# buck.net
KiCad netlist of a schematic drawn in Altium Designer
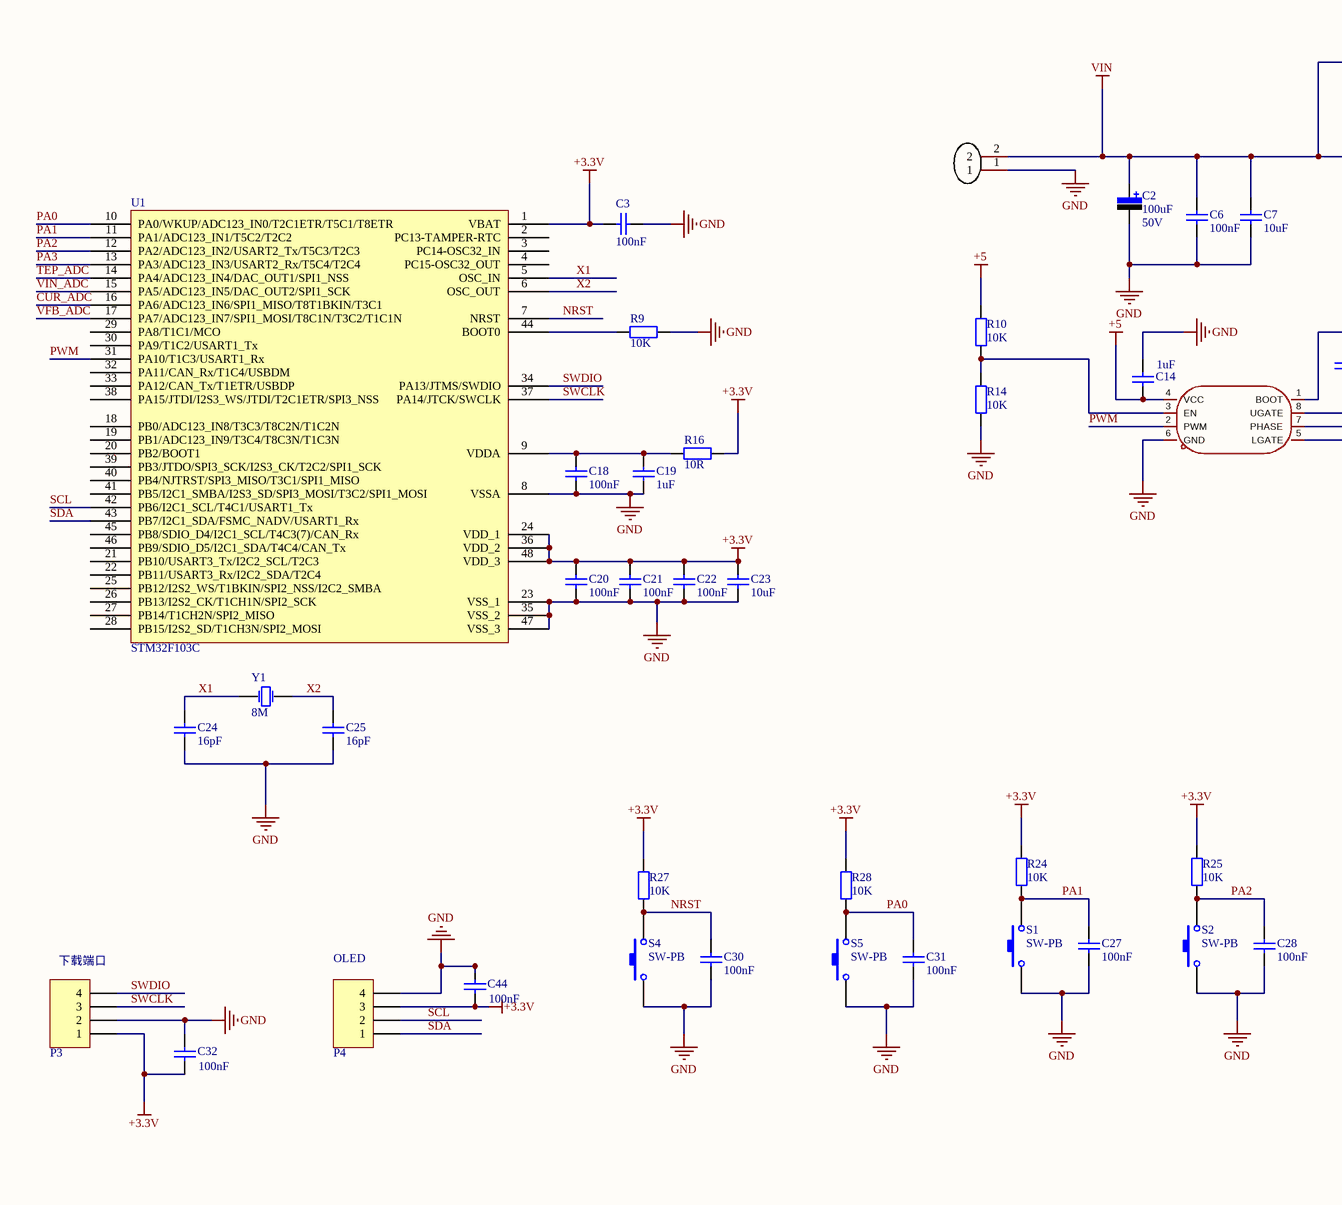
[diagram p0: buck.SchDoc, left]
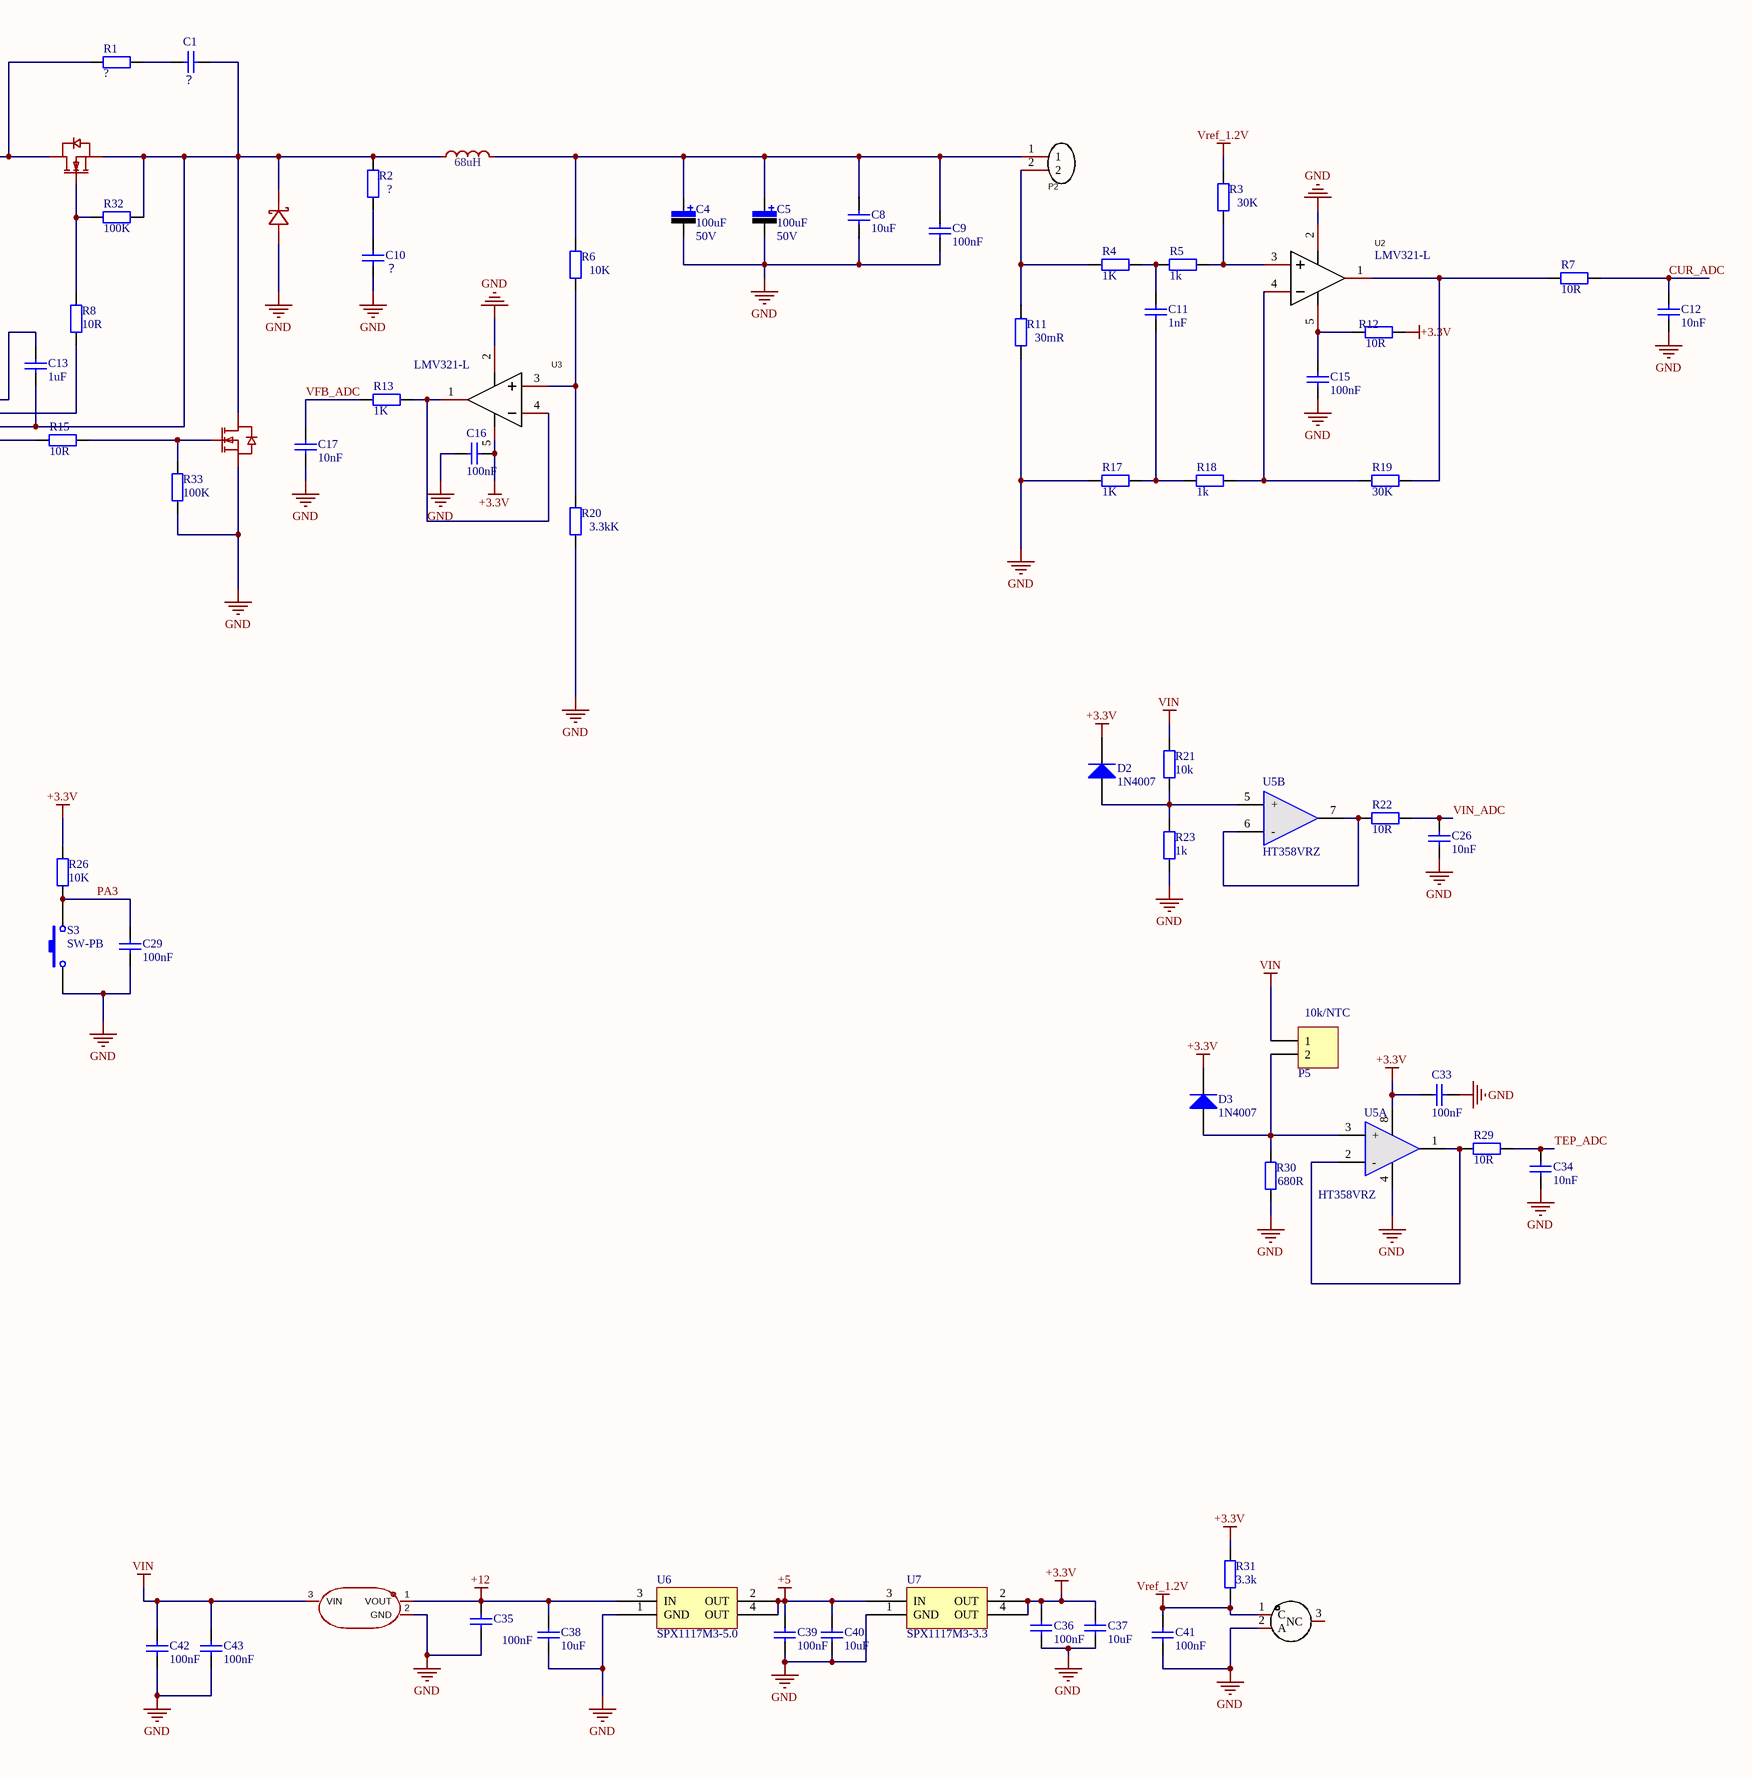
[diagram p1: buck.SchDoc, right]

(export (version "E")
  (design (tool "Eeschema 10.0.6"))
  (components
    (comp (ref "C1")
      (value "？")
      (footprint "C-RAD-0603")
      (description "无极性电容")
      (fields (field (name "PUBLISHER") "Altium Limited"))
      (libsource (lib "fszhang") (part "Cap"))
    )
    (comp (ref "C2")
      (value "100uF")
      (footprint "CAP-TH_BD6.0-P2.50-D0.5-FD")
      (description "极性电解电容")
      (fields
        (field (name "VOL") "50V")
        (field (name "Comment") "Cap Pol")
        (field (name "PUBLISHER") "Altium Limited")
      )
      (libsource (lib "fszhang") (part "Cap Pol"))
    )
    (comp (ref "C3")
      (value "100nF")
      (footprint "C-RAD-0603")
      (description "无极性电容")
      (fields (field (name "PUBLISHER") "Altium Limited"))
      (libsource (lib "fszhang") (part "Cap"))
    )
    (comp (ref "C4")
      (value "100uF")
      (footprint "CAP-TH_BD6.0-P2.50-D0.5-FD")
      (description "极性电解电容")
      (fields
        (field (name "VOL") "50V")
        (field (name "Comment") "Cap Pol")
        (field (name "PUBLISHER") "Altium Limited")
      )
      (libsource (lib "fszhang") (part "Cap Pol"))
    )
    (comp (ref "C5")
      (value "100uF")
      (footprint "CAP-TH_BD6.0-P2.50-D0.5-FD")
      (description "极性电解电容")
      (fields
        (field (name "VOL") "50V")
        (field (name "Comment") "Cap Pol")
        (field (name "PUBLISHER") "Altium Limited")
      )
      (libsource (lib "fszhang") (part "Cap Pol"))
    )
    (comp (ref "C6")
      (value "100nF")
      (footprint "C-RAD-0603")
      (description "无极性电容")
      (fields (field (name "PUBLISHER") "Altium Limited"))
      (libsource (lib "fszhang") (part "Cap"))
    )
    (comp (ref "C7")
      (value "10uF")
      (footprint "C-RAD-0603")
      (description "无极性电容")
      (fields (field (name "PUBLISHER") "Altium Limited"))
      (libsource (lib "fszhang") (part "Cap"))
    )
    (comp (ref "C8")
      (value "10uF")
      (footprint "C-RAD-0603")
      (description "无极性电容")
      (fields (field (name "PUBLISHER") "Altium Limited"))
      (libsource (lib "fszhang") (part "Cap"))
    )
    (comp (ref "C9")
      (value "100nF")
      (footprint "C-RAD-0603")
      (description "无极性电容")
      (fields (field (name "PUBLISHER") "Altium Limited"))
      (libsource (lib "fszhang") (part "Cap"))
    )
    (comp (ref "C10")
      (value "？")
      (footprint "C-RAD-0603")
      (description "无极性电容")
      (fields (field (name "PUBLISHER") "Altium Limited"))
      (libsource (lib "fszhang") (part "Cap"))
    )
    (comp (ref "C11")
      (value "1nF")
      (footprint "C-RAD-0603")
      (description "无极性电容")
      (fields (field (name "PUBLISHER") "Altium Limited"))
      (libsource (lib "fszhang") (part "Cap"))
    )
    (comp (ref "C12")
      (value "10nF")
      (footprint "C-RAD-0603")
      (description "无极性电容")
      (fields (field (name "PUBLISHER") "Altium Limited"))
      (libsource (lib "fszhang") (part "Cap"))
    )
    (comp (ref "C13")
      (value "1uF")
      (footprint "C-RAD-0603")
      (description "无极性电容")
      (fields (field (name "PUBLISHER") "Altium Limited"))
      (libsource (lib "fszhang") (part "Cap"))
    )
    (comp (ref "C14")
      (value "1uF")
      (footprint "C-RAD-0603")
      (description "无极性电容")
      (fields (field (name "PUBLISHER") "Altium Limited"))
      (libsource (lib "fszhang") (part "Cap"))
    )
    (comp (ref "C15")
      (value "100nF")
      (footprint "C-RAD-0603")
      (description "无极性电容")
      (fields (field (name "PUBLISHER") "Altium Limited"))
      (libsource (lib "fszhang") (part "Cap"))
    )
    (comp (ref "C16")
      (value "100nF")
      (footprint "C-RAD-0603")
      (description "无极性电容")
      (fields (field (name "PUBLISHER") "Altium Limited"))
      (libsource (lib "fszhang") (part "Cap"))
    )
    (comp (ref "C17")
      (value "10nF")
      (footprint "C-RAD-0603")
      (description "无极性电容")
      (fields (field (name "PUBLISHER") "Altium Limited"))
      (libsource (lib "fszhang") (part "Cap"))
    )
    (comp (ref "C18")
      (value "100nF")
      (footprint "C-RAD-0603")
      (description "无极性电容")
      (fields (field (name "PUBLISHER") "Altium Limited"))
      (libsource (lib "fszhang") (part "Cap"))
    )
    (comp (ref "C19")
      (value "1uF")
      (footprint "C-RAD-0603")
      (description "无极性电容")
      (fields (field (name "PUBLISHER") "Altium Limited"))
      (libsource (lib "fszhang") (part "Cap"))
    )
    (comp (ref "C20")
      (value "100nF")
      (footprint "C-RAD-0603")
      (description "无极性电容")
      (fields (field (name "PUBLISHER") "Altium Limited"))
      (libsource (lib "fszhang") (part "Cap"))
    )
    (comp (ref "C21")
      (value "100nF")
      (footprint "C-RAD-0603")
      (description "无极性电容")
      (fields (field (name "PUBLISHER") "Altium Limited"))
      (libsource (lib "fszhang") (part "Cap"))
    )
    (comp (ref "C22")
      (value "100nF")
      (footprint "C-RAD-0603")
      (description "无极性电容")
      (fields (field (name "PUBLISHER") "Altium Limited"))
      (libsource (lib "fszhang") (part "Cap"))
    )
    (comp (ref "C23")
      (value "10uF")
      (footprint "C-RAD-0603")
      (description "无极性电容")
      (fields (field (name "PUBLISHER") "Altium Limited"))
      (libsource (lib "fszhang") (part "Cap"))
    )
    (comp (ref "C24")
      (value "16pF")
      (footprint "C-RAD-0603")
      (description "无极性电容")
      (fields (field (name "PUBLISHER") "Altium Limited"))
      (libsource (lib "fszhang") (part "Cap"))
    )
    (comp (ref "C25")
      (value "16pF")
      (footprint "C-RAD-0603")
      (description "无极性电容")
      (fields (field (name "PUBLISHER") "Altium Limited"))
      (libsource (lib "fszhang") (part "Cap"))
    )
    (comp (ref "C26")
      (value "10nF")
      (footprint "C-RAD-0603")
      (description "无极性电容")
      (fields (field (name "PUBLISHER") "Altium Limited"))
      (libsource (lib "fszhang") (part "Cap"))
    )
    (comp (ref "C27")
      (value "100nF")
      (footprint "C-RAD-0603")
      (description "无极性电容")
      (fields (field (name "PUBLISHER") "Altium Limited"))
      (libsource (lib "fszhang") (part "Cap"))
    )
    (comp (ref "C28")
      (value "100nF")
      (footprint "C-RAD-0603")
      (description "无极性电容")
      (fields (field (name "PUBLISHER") "Altium Limited"))
      (libsource (lib "fszhang") (part "Cap"))
    )
    (comp (ref "C29")
      (value "100nF")
      (footprint "C-RAD-0603")
      (description "无极性电容")
      (fields (field (name "PUBLISHER") "Altium Limited"))
      (libsource (lib "fszhang") (part "Cap"))
    )
    (comp (ref "C30")
      (value "100nF")
      (footprint "C-RAD-0603")
      (description "无极性电容")
      (fields (field (name "PUBLISHER") "Altium Limited"))
      (libsource (lib "fszhang") (part "Cap"))
    )
    (comp (ref "C31")
      (value "100nF")
      (footprint "C-RAD-0603")
      (description "无极性电容")
      (fields (field (name "PUBLISHER") "Altium Limited"))
      (libsource (lib "fszhang") (part "Cap"))
    )
    (comp (ref "C32")
      (value "100nF")
      (footprint "C-RAD-0603")
      (description "无极性电容")
      (fields (field (name "PUBLISHER") "Altium Limited"))
      (libsource (lib "fszhang") (part "Cap"))
    )
    (comp (ref "C33")
      (value "100nF")
      (footprint "C-RAD-0603")
      (description "无极性电容")
      (fields (field (name "PUBLISHER") "Altium Limited"))
      (libsource (lib "fszhang") (part "Cap"))
    )
    (comp (ref "C34")
      (value "10nF")
      (footprint "C-RAD-0603")
      (description "无极性电容")
      (fields (field (name "PUBLISHER") "Altium Limited"))
      (libsource (lib "fszhang") (part "Cap"))
    )
    (comp (ref "C35")
      (value "100nF")
      (footprint "C-RAD-0603")
      (description "无极性电容")
      (fields (field (name "PUBLISHER") "Altium Limited"))
      (libsource (lib "fszhang") (part "Cap"))
    )
    (comp (ref "C36")
      (value "100nF")
      (footprint "C-RAD-0603")
      (description "无极性电容")
      (fields (field (name "PUBLISHER") "Altium Limited"))
      (libsource (lib "fszhang") (part "Cap"))
    )
    (comp (ref "C37")
      (value "10uF")
      (footprint "C-RAD-0603")
      (description "无极性电容")
      (fields (field (name "PUBLISHER") "Altium Limited"))
      (libsource (lib "fszhang") (part "Cap"))
    )
    (comp (ref "C38")
      (value "10uF")
      (footprint "C-RAD-0603")
      (description "无极性电容")
      (fields (field (name "PUBLISHER") "Altium Limited"))
      (libsource (lib "fszhang") (part "Cap"))
    )
    (comp (ref "C39")
      (value "100nF")
      (footprint "C-RAD-0603")
      (description "无极性电容")
      (fields (field (name "PUBLISHER") "Altium Limited"))
      (libsource (lib "fszhang") (part "Cap"))
    )
    (comp (ref "C40")
      (value "10uF")
      (footprint "C-RAD-0603")
      (description "无极性电容")
      (fields (field (name "PUBLISHER") "Altium Limited"))
      (libsource (lib "fszhang") (part "Cap"))
    )
    (comp (ref "C41")
      (value "100nF")
      (footprint "C-RAD-0603")
      (description "无极性电容")
      (fields (field (name "PUBLISHER") "Altium Limited"))
      (libsource (lib "fszhang") (part "Cap"))
    )
    (comp (ref "C42")
      (value "100nF")
      (footprint "C-RAD-0603")
      (description "无极性电容")
      (fields (field (name "PUBLISHER") "Altium Limited"))
      (libsource (lib "fszhang") (part "Cap"))
    )
    (comp (ref "C43")
      (value "100nF")
      (footprint "C-RAD-0603")
      (description "无极性电容")
      (fields (field (name "PUBLISHER") "Altium Limited"))
      (libsource (lib "fszhang") (part "Cap"))
    )
    (comp (ref "C44")
      (value "100nF")
      (footprint "C-RAD-0603")
      (description "无极性电容")
      (fields (field (name "PUBLISHER") "Altium Limited"))
      (libsource (lib "fszhang") (part "Cap"))
    )
    (comp (ref "D1")
      (value "ss54f_c18199179")
      (footprint "SMAF_L3.5-W2.6-LS4.7-RD-1")
      (description "二极管配置:独立式;正向压降(Vf):550mV@5.0A;直流反向耐压(Vr):40V;整流电流:5A;")
      (fields (field (name "MANUFACTURER") "R+O(宏嘉诚)") (field (name "MANUFACTURERPART") "SS54F"))
      (libsource (lib "fszhang") (part "SS54F"))
    )
    (comp (ref "D2")
      (value "Diode")
      (footprint "SMA_L4.3-W2.6-LS5.0-FD")
      (description "二极管")
      (fields (field (name "TYPE") "1N4007") (field (name "PUBLISHER") "Altium Limited"))
      (libsource (lib "fszhang") (part "Diode"))
    )
    (comp (ref "D3")
      (value "Diode")
      (footprint "SMA_L4.3-W2.6-LS5.0-FD")
      (description "二极管")
      (fields (field (name "TYPE") "1N4007") (field (name "PUBLISHER") "Altium Limited"))
      (libsource (lib "fszhang") (part "Diode"))
    )
    (comp (ref "L1")
      (value "68uH")
      (footprint "IND-SMD_L11.5-W10.1_XR1050-680M")
      (description "电感值:68uH;精度:±20%;额定电流:3A;饱和电流(Isat):3.8A;")
      (fields (field (name "MANUFACTURER") "XR(祥如)") (field (name "MANUFACTURERPART") "XR1050-680M"))
      (libsource (lib "fszhang") (part "xr1050-680m"))
    )
    (comp (ref "P1")
      (value "WJ500V-5.08-2P")
      (footprint "CONN-TH_2P-P5.00_WJ500V-5.08-2P")
      (description "接线端子")
      (fields (field (name "MANUFACTURER") "KANGNEX(康奈克斯电气)"))
      (libsource (lib "fszhang") (part "WJ500V-5.08-2P"))
    )
    (comp (ref "P2")
      (value "WJ500V-5.08-2P")
      (footprint "CONN-TH_2P-P5.00_WJ500V-5.08-2P")
      (description "接线端子")
      (fields (field (name "MANUFACTURER") "KANGNEX(康奈克斯电气)"))
      (libsource (lib "fszhang") (part "WJ500V-5.08-2P"))
    )
    (comp (ref "P3")
      (value "Header 4")
      (footprint "HDR4X1_A")
      (description "接插件")
      (fields (field (name "PUBLISHER") "Altium Limited"))
      (libsource (lib "fszhang") (part "Header 4"))
    )
    (comp (ref "P4")
      (value "Header 4")
      (footprint "HDR4X1_A")
      (description "接插件")
      (fields (field (name "PUBLISHER") "Altium Limited"))
      (libsource (lib "fszhang") (part "Header 4"))
    )
    (comp (ref "P5")
      (value "Header 2")
      (footprint "HDR2X1_A")
      (description "接插件")
      (fields (field (name "PUBLISHER") "Altium Limited"))
      (libsource (lib "fszhang") (part "Header 2"))
    )
    (comp (ref "Q1")
      (value "xr20n04")
      (footprint "TO-252-3L_L6.6-W6.1-P4.60-LS9.5-BR-CW")
      (description "数量:1个N沟道;漏源电压(Vdss):40V;连续漏极电流(Id):20A;导通电阻(RDS(on)):40mΩ@10V;耗散功率(Pd):4W;阈值电压(Vgs(th)):2.2V;")
      (fields (field (name "MANUFACTURER") "XNRUSEMI(新锐)") (field (name "MANUFACTURERPART") "XR20N04"))
      (libsource (lib "fszhang") (part "XR20N04"))
    )
    (comp (ref "Q2")
      (value "xr20n04")
      (footprint "TO-252-3L_L6.6-W6.1-P4.60-LS9.5-BR-CW")
      (description "数量:1个N沟道;漏源电压(Vdss):40V;连续漏极电流(Id):20A;导通电阻(RDS(on)):40mΩ@10V;耗散功率(Pd):4W;阈值电压(Vgs(th)):2.2V;")
      (fields (field (name "MANUFACTURER") "XNRUSEMI(新锐)") (field (name "MANUFACTURERPART") "XR20N04"))
      (libsource (lib "fszhang") (part "XR20N04"))
    )
    (comp (ref "R1")
      (value "?")
      (footprint "0603-1")
      (description "贴片电阻")
      (fields (field (name "PUBLISHER") "Altium Limited"))
      (libsource (lib "fszhang") (part "Res1"))
    )
    (comp (ref "R2")
      (value "?")
      (footprint "0603-1")
      (description "贴片电阻")
      (fields (field (name "PUBLISHER") "Altium Limited"))
      (libsource (lib "") (part "Res1_2"))
    )
    (comp (ref "R3")
      (value "30K")
      (footprint "0603-1")
      (description "贴片电阻")
      (fields (field (name "PUBLISHER") "Altium Limited"))
      (libsource (lib "") (part "Res1_2"))
    )
    (comp (ref "R4")
      (value "1K")
      (footprint "0603-1")
      (description "贴片电阻")
      (fields (field (name "PUBLISHER") "Altium Limited"))
      (libsource (lib "fszhang") (part "Res1"))
    )
    (comp (ref "R5")
      (value "1k")
      (footprint "0603-1")
      (description "贴片电阻")
      (fields (field (name "PUBLISHER") "Altium Limited"))
      (libsource (lib "fszhang") (part "Res1"))
    )
    (comp (ref "R6")
      (value "10K")
      (footprint "0603-1")
      (description "贴片电阻")
      (fields (field (name "PUBLISHER") "Altium Limited"))
      (libsource (lib "") (part "Res1_2"))
    )
    (comp (ref "R7")
      (value "10R")
      (footprint "0603-1")
      (description "贴片电阻")
      (fields (field (name "PUBLISHER") "Altium Limited"))
      (libsource (lib "") (part "Res1_2"))
    )
    (comp (ref "R8")
      (value "10R")
      (footprint "0603-1")
      (description "贴片电阻")
      (fields (field (name "PUBLISHER") "Altium Limited"))
      (libsource (lib "") (part "Res1_2"))
    )
    (comp (ref "R9")
      (value "10K")
      (footprint "0603-1")
      (description "贴片电阻")
      (fields (field (name "PUBLISHER") "Altium Limited"))
      (libsource (lib "") (part "Res1_1"))
    )
    (comp (ref "R10")
      (value "10K")
      (footprint "0603-1")
      (description "贴片电阻")
      (fields (field (name "PUBLISHER") "Altium Limited"))
      (libsource (lib "") (part "Res1_3"))
    )
    (comp (ref "R11")
      (value "30mR")
      (footprint "2512")
      (description "贴片电阻")
      (fields (field (name "PUBLISHER") "Altium Limited"))
      (libsource (lib "") (part "Res1_2"))
    )
    (comp (ref "R12")
      (value "10R")
      (footprint "0603-1")
      (description "贴片电阻")
      (fields (field (name "PUBLISHER") "Altium Limited"))
      (libsource (lib "fszhang") (part "Res1"))
    )
    (comp (ref "R13")
      (value "1K")
      (footprint "0603-1")
      (description "贴片电阻")
      (fields (field (name "PUBLISHER") "Altium Limited"))
      (libsource (lib "fszhang") (part "Res1"))
    )
    (comp (ref "R14")
      (value "10K")
      (footprint "0603-1")
      (description "贴片电阻")
      (fields (field (name "PUBLISHER") "Altium Limited"))
      (libsource (lib "") (part "Res1_3"))
    )
    (comp (ref "R15")
      (value "10R")
      (footprint "0603-1")
      (description "贴片电阻")
      (fields (field (name "PUBLISHER") "Altium Limited"))
      (libsource (lib "fszhang") (part "Res1"))
    )
    (comp (ref "R16")
      (value "10R")
      (footprint "0603-1")
      (description "贴片电阻")
      (fields (field (name "PUBLISHER") "Altium Limited"))
      (libsource (lib "") (part "Res1_1"))
    )
    (comp (ref "R17")
      (value "1K")
      (footprint "0603-1")
      (description "贴片电阻")
      (fields (field (name "PUBLISHER") "Altium Limited"))
      (libsource (lib "fszhang") (part "Res1"))
    )
    (comp (ref "R18")
      (value "1k")
      (footprint "0603-1")
      (description "贴片电阻")
      (fields (field (name "PUBLISHER") "Altium Limited"))
      (libsource (lib "fszhang") (part "Res1"))
    )
    (comp (ref "R19")
      (value "30K")
      (footprint "0603-1")
      (description "贴片电阻")
      (fields (field (name "PUBLISHER") "Altium Limited"))
      (libsource (lib "fszhang") (part "Res1"))
    )
    (comp (ref "R20")
      (value "3.3kK")
      (footprint "0603-1")
      (description "贴片电阻")
      (fields (field (name "PUBLISHER") "Altium Limited"))
      (libsource (lib "") (part "Res1_2"))
    )
    (comp (ref "R21")
      (value "10k")
      (footprint "0603-1")
      (description "贴片电阻")
      (fields (field (name "PUBLISHER") "Altium Limited"))
      (libsource (lib "") (part "Res1_3"))
    )
    (comp (ref "R22")
      (value "10R")
      (footprint "0603-1")
      (description "贴片电阻")
      (fields (field (name "PUBLISHER") "Altium Limited"))
      (libsource (lib "") (part "Res1_1"))
    )
    (comp (ref "R23")
      (value "1k")
      (footprint "0603-1")
      (description "贴片电阻")
      (fields (field (name "PUBLISHER") "Altium Limited"))
      (libsource (lib "") (part "Res1_3"))
    )
    (comp (ref "R24")
      (value "10K")
      (footprint "0603-1")
      (description "贴片电阻")
      (fields (field (name "PUBLISHER") "Altium Limited"))
      (libsource (lib "") (part "Res1_2"))
    )
    (comp (ref "R25")
      (value "10K")
      (footprint "0603-1")
      (description "贴片电阻")
      (fields (field (name "PUBLISHER") "Altium Limited"))
      (libsource (lib "") (part "Res1_2"))
    )
    (comp (ref "R26")
      (value "10K")
      (footprint "0603-1")
      (description "贴片电阻")
      (fields (field (name "PUBLISHER") "Altium Limited"))
      (libsource (lib "") (part "Res1_2"))
    )
    (comp (ref "R27")
      (value "10K")
      (footprint "0603-1")
      (description "贴片电阻")
      (fields (field (name "PUBLISHER") "Altium Limited"))
      (libsource (lib "") (part "Res1_2"))
    )
    (comp (ref "R28")
      (value "10K")
      (footprint "0603-1")
      (description "贴片电阻")
      (fields (field (name "PUBLISHER") "Altium Limited"))
      (libsource (lib "") (part "Res1_2"))
    )
    (comp (ref "R29")
      (value "10R")
      (footprint "0603-1")
      (description "贴片电阻")
      (fields (field (name "PUBLISHER") "Altium Limited"))
      (libsource (lib "") (part "Res1_1"))
    )
    (comp (ref "R30")
      (value "680R")
      (footprint "0603-1")
      (description "贴片电阻")
      (fields (field (name "PUBLISHER") "Altium Limited"))
      (libsource (lib "") (part "Res1_3"))
    )
    (comp (ref "R31")
      (value "3.3k")
      (footprint "0603-1")
      (description "贴片电阻")
      (fields (field (name "PUBLISHER") "Altium Limited"))
      (libsource (lib "") (part "Res1_1"))
    )
    (comp (ref "R32")
      (value "100K")
      (footprint "0603-1")
      (description "贴片电阻")
      (fields (field (name "PUBLISHER") "Altium Limited"))
      (libsource (lib "fszhang") (part "Res1"))
    )
    (comp (ref "R33")
      (value "100K")
      (footprint "0603-1")
      (description "贴片电阻")
      (fields (field (name "PUBLISHER") "Altium Limited"))
      (libsource (lib "") (part "Res1_3"))
    )
    (comp (ref "S1")
      (value "SW-PB")
      (footprint "SW_PB2_A1")
      (description "微动开关")
      (fields (field (name "PUBLISHER") "Altium Limited"))
      (libsource (lib "fszhang") (part "SW-PB"))
    )
    (comp (ref "S2")
      (value "SW-PB")
      (footprint "SW_PB2_A1")
      (description "微动开关")
      (fields (field (name "PUBLISHER") "Altium Limited"))
      (libsource (lib "fszhang") (part "SW-PB"))
    )
    (comp (ref "S3")
      (value "SW-PB")
      (footprint "SW_PB2_A1")
      (description "微动开关")
      (fields (field (name "PUBLISHER") "Altium Limited"))
      (libsource (lib "fszhang") (part "SW-PB"))
    )
    (comp (ref "S4")
      (value "SW-PB")
      (footprint "SW_PB2_A1")
      (description "微动开关")
      (fields (field (name "PUBLISHER") "Altium Limited"))
      (libsource (lib "fszhang") (part "SW-PB"))
    )
    (comp (ref "S5")
      (value "SW-PB")
      (footprint "SW_PB2_A1")
      (description "微动开关")
      (fields (field (name "PUBLISHER") "Altium Limited"))
      (libsource (lib "fszhang") (part "SW-PB"))
    )
    (comp (ref "U1")
      (value "STM32F103C")
      (footprint "LQFP-48_M")
      (description "STM32单片机48引脚")
      (libsource (lib "fszhang") (part "STM32F103C"))
    )
    (comp (ref "U2")
      (value "LMV321-L")
      (footprint "SOT-23-5_L3.0-W1.7-P0.95-LS2.8-BR")
      (description "比较器")
      (fields (field (name "MANUFACTURER") "TI(德州仪器)") (field (name "MANUFACTURER PART") "TLV3201AIDBVR"))
      (libsource (lib "fszhang") (part "TLV3201AIDBVR"))
    )
    (comp (ref "U3")
      (value "LMV321-L")
      (footprint "SOT-23-5_L3.0-W1.7-P0.95-LS2.8-BR")
      (description "比较器")
      (fields (field (name "MANUFACTURER") "TI(德州仪器)") (field (name "MANUFACTURER PART") "TLV3201AIDBVR"))
      (libsource (lib "fszhang") (part "TLV3201AIDBVR"))
    )
    (comp (ref "U4")
      (value "RT9624AZS")
      (footprint "SOP-8_L4.9-W3.9-P1.27-LS6.0-BL-1")
      (fields (field (name "MANUFACTURER") "RICHTEK(立锜)"))
      (libsource (lib "fszhang") (part "RT9624AZS"))
    )
    (comp (ref "U5")
      (value "HT358VRZ")
      (footprint "NSO8_N")
      (description "双运放")
      (libsource (lib "fszhang") (part "LM358"))
    )
    (comp (ref "U6")
      (value "SPX1117M3-5.0")
      (footprint "SOT-223")
      (description "5.0V稳压芯片")
      (libsource (lib "fszhang") (part "SPX1117M3-5.0"))
    )
    (comp (ref "U7")
      (value "SPX1117M3-3.3")
      (footprint "SOT-223")
      (description "3.3V稳压芯片")
      (libsource (lib "fszhang") (part "SPX1117M3-3.3"))
    )
    (comp (ref "U8")
      (value "MG78M12N3")
      (footprint "SOT-89-3_L4.5-W2.5-P1.50-LS4.2-BR")
      (description "最大30V转12V，压差当电压大于3V时为1.8v，小于3V时为2.3V")
      (fields (field (name "MANUFACTURER") "Megain(美佳音)"))
      (libsource (lib "fszhang") (part "MG78M12N3"))
    )
    (comp (ref "U9")
      (value "LM385M3-1.2/TR")
      (footprint "SOT-23-3_L2.9-W1.3-P1.90-LS2.4-BR")
      (fields (field (name "MANUFACTURER") "HGSEMI(华冠)"))
      (libsource (lib "fszhang") (part "LM385M3-1.2/TR"))
    )
    (comp (ref "Y1")
      (value "8M")
      (footprint "X-SM49")
      (description "晶振")
      (fields (field (name "Comment") "XTAL") (field (name "PUBLISHER") "Altium Limited"))
      (libsource (lib "fszhang") (part "XTAL"))
    )
  )
  (nets
    (net (code "1") (name "+3.3V") (class "Default")
      (node (ref "C16") (pin "2") (pinfunction "2_2") (pintype "passive"))
      (node (ref "C20") (pin "2") (pinfunction "2_2") (pintype "passive"))
      (node (ref "C21") (pin "2") (pinfunction "2_2") (pintype "passive"))
      (node (ref "C22") (pin "2") (pinfunction "2_2") (pintype "passive"))
      (node (ref "C23") (pin "2") (pinfunction "2_2") (pintype "passive"))
      (node (ref "C3") (pin "1") (pinfunction "1_1") (pintype "passive"))
      (node (ref "C32") (pin "1") (pinfunction "1_1") (pintype "passive"))
      (node (ref "C33") (pin "2") (pinfunction "2_2") (pintype "passive"))
      (node (ref "C36") (pin "2") (pinfunction "2_2") (pintype "passive"))
      (node (ref "C37") (pin "2") (pinfunction "2_2") (pintype "passive"))
      (node (ref "C44") (pin "1") (pinfunction "1_1") (pintype "passive"))
      (node (ref "D2") (pin "2") (pinfunction "K_2") (pintype "passive"))
      (node (ref "D3") (pin "2") (pinfunction "K_2") (pintype "passive"))
      (node (ref "P3") (pin "1") (pinfunction "1_1") (pintype "passive"))
      (node (ref "P4") (pin "3") (pinfunction "3_3") (pintype "passive"))
      (node (ref "R12") (pin "1") (pinfunction "1_1") (pintype "passive"))
      (node (ref "R16") (pin "2") (pinfunction "2_2") (pintype "passive"))
      (node (ref "R24") (pin "2") (pinfunction "2_2") (pintype "passive"))
      (node (ref "R25") (pin "2") (pinfunction "2_2") (pintype "passive"))
      (node (ref "R26") (pin "2") (pinfunction "2_2") (pintype "passive"))
      (node (ref "R27") (pin "2") (pinfunction "2_2") (pintype "passive"))
      (node (ref "R28") (pin "2") (pinfunction "2_2") (pintype "passive"))
      (node (ref "R31") (pin "2") (pinfunction "2_2") (pintype "passive"))
      (node (ref "U1") (pin "1") (pinfunction "VBAT_1") (pintype "passive"))
      (node (ref "U1") (pin "24") (pinfunction "VDD_1_24") (pintype "passive"))
      (node (ref "U1") (pin "36") (pinfunction "VDD_2_36") (pintype "passive"))
      (node (ref "U1") (pin "48") (pinfunction "VDD_3_48") (pintype "passive"))
      (node (ref "U3") (pin "5") (pinfunction "VCC_5") (pintype "passive"))
      (node (ref "U5") (pin "8") (pinfunction "V+_8") (pintype "power_in"))
      (node (ref "U7") (pin "2") (pinfunction "OUT_2") (pintype "passive"))
      (node (ref "U7") (pin "4") (pinfunction "OUT_4") (pintype "passive"))
    )
    (net (code "2") (name "+5") (class "Default")
      (node (ref "C14") (pin "1") (pinfunction "1_1") (pintype "passive"))
      (node (ref "C39") (pin "2") (pinfunction "2_2") (pintype "passive"))
      (node (ref "C40") (pin "2") (pinfunction "2_2") (pintype "passive"))
      (node (ref "R10") (pin "1") (pinfunction "1_1") (pintype "passive"))
      (node (ref "U4") (pin "4") (pinfunction "VCC_4") (pintype "passive"))
      (node (ref "U6") (pin "2") (pinfunction "OUT_2") (pintype "passive"))
      (node (ref "U6") (pin "4") (pinfunction "OUT_4") (pintype "passive"))
      (node (ref "U7") (pin "3") (pinfunction "IN_3") (pintype "passive"))
    )
    (net (code "3") (name "+12") (class "Default")
      (node (ref "C35") (pin "1") (pinfunction "1_1") (pintype "passive"))
      (node (ref "C38") (pin "2") (pinfunction "2_2") (pintype "passive"))
      (node (ref "U6") (pin "3") (pinfunction "IN_3") (pintype "passive"))
      (node (ref "U8") (pin "1") (pinfunction "VOUT_1") (pintype "passive"))
    )
    (net (code "4") (name "/CUR_ADC") (class "Default")
      (node (ref "C12") (pin "2") (pinfunction "2_2") (pintype "passive"))
      (node (ref "R7") (pin "2") (pinfunction "2_2") (pintype "passive"))
      (node (ref "U1") (pin "16") (pinfunction "PA6/ADC123_IN6/SPI1_MISO/T8T1BKIN/T3C1_16") (pintype "passive"))
    )
    (net (code "5") (name "/NRST") (class "Default")
      (node (ref "C30") (pin "2") (pinfunction "2_2") (pintype "passive"))
      (node (ref "R27") (pin "1") (pinfunction "1_1") (pintype "passive"))
      (node (ref "S4") (pin "2") (pinfunction "2_2") (pintype "passive"))
      (node (ref "U1") (pin "7") (pinfunction "NRST_7") (pintype "passive"))
    )
    (net (code "6") (name "/PA0") (class "Default")
      (node (ref "C31") (pin "2") (pinfunction "2_2") (pintype "passive"))
      (node (ref "R28") (pin "1") (pinfunction "1_1") (pintype "passive"))
      (node (ref "S5") (pin "2") (pinfunction "2_2") (pintype "passive"))
      (node (ref "U1") (pin "10") (pinfunction "PA0/WKUP/ADC123_IN0/T2C1ETR/T5C1/T8ETR_10") (pintype "passive"))
    )
    (net (code "7") (name "/PA1") (class "Default")
      (node (ref "C27") (pin "2") (pinfunction "2_2") (pintype "passive"))
      (node (ref "R24") (pin "1") (pinfunction "1_1") (pintype "passive"))
      (node (ref "S1") (pin "2") (pinfunction "2_2") (pintype "passive"))
      (node (ref "U1") (pin "11") (pinfunction "PA1/ADC123_IN1/T5C2/T2C2_11") (pintype "passive"))
    )
    (net (code "8") (name "/PA2") (class "Default")
      (node (ref "C28") (pin "2") (pinfunction "2_2") (pintype "passive"))
      (node (ref "R25") (pin "1") (pinfunction "1_1") (pintype "passive"))
      (node (ref "S2") (pin "2") (pinfunction "2_2") (pintype "passive"))
      (node (ref "U1") (pin "12") (pinfunction "PA2/ADC123_IN2/USART2_Tx/T5C3/T2C3_12") (pintype "passive"))
    )
    (net (code "9") (name "/PA3") (class "Default")
      (node (ref "C29") (pin "2") (pinfunction "2_2") (pintype "passive"))
      (node (ref "R26") (pin "1") (pinfunction "1_1") (pintype "passive"))
      (node (ref "S3") (pin "2") (pinfunction "2_2") (pintype "passive"))
      (node (ref "U1") (pin "13") (pinfunction "PA3/ADC123_IN3/USART2_Rx/T5C4/T2C4_13") (pintype "passive"))
    )
    (net (code "10") (name "/PWM") (class "Default")
      (node (ref "U1") (pin "31") (pinfunction "PA10/T1C3/USART1_Rx_31") (pintype "passive"))
      (node (ref "U4") (pin "2") (pinfunction "PWM_2") (pintype "passive"))
    )
    (net (code "11") (name "/SCL") (class "Default")
      (node (ref "P4") (pin "2") (pinfunction "2_2") (pintype "passive"))
      (node (ref "U1") (pin "42") (pinfunction "PB6/I2C1_SCL/T4C1/USART1_Tx_42") (pintype "passive"))
    )
    (net (code "12") (name "/SDA") (class "Default")
      (node (ref "P4") (pin "1") (pinfunction "1_1") (pintype "passive"))
      (node (ref "U1") (pin "43") (pinfunction "PB7/I2C1_SDA/FSMC_NADV/USART1_Rx_43") (pintype "passive"))
    )
    (net (code "13") (name "/SWCLK") (class "Default")
      (node (ref "P3") (pin "3") (pinfunction "3_3") (pintype "passive"))
      (node (ref "U1") (pin "37") (pinfunction "PA14/JTCK/SWCLK_37") (pintype "passive"))
    )
    (net (code "14") (name "/SWDIO") (class "Default")
      (node (ref "P3") (pin "4") (pinfunction "4_4") (pintype "passive"))
      (node (ref "U1") (pin "34") (pinfunction "PA13/JTMS/SWDIO_34") (pintype "passive"))
    )
    (net (code "15") (name "/TEP_ADC") (class "Default")
      (node (ref "C34") (pin "2") (pinfunction "2_2") (pintype "passive"))
      (node (ref "R29") (pin "2") (pinfunction "2_2") (pintype "passive"))
      (node (ref "U1") (pin "14") (pinfunction "PA4/ADC123_IN4/DAC_OUT1/SPI1_NSS_14") (pintype "passive"))
    )
    (net (code "16") (name "/VFB_ADC") (class "Default")
      (node (ref "C17") (pin "1") (pinfunction "1_1") (pintype "passive"))
      (node (ref "R13") (pin "2") (pinfunction "2_2") (pintype "passive"))
      (node (ref "U1") (pin "17") (pinfunction "PA7/ADC123_IN7/SPI1_MOSI/T8C1N/T3C2/T1C1N_17") (pintype "passive"))
    )
    (net (code "17") (name "/VIN_ADC") (class "Default")
      (node (ref "C26") (pin "2") (pinfunction "2_2") (pintype "passive"))
      (node (ref "R22") (pin "2") (pinfunction "2_2") (pintype "passive"))
      (node (ref "U1") (pin "15") (pinfunction "PA5/ADC123_IN5/DAC_OUT2/SPI1_SCK_15") (pintype "passive"))
    )
    (net (code "18") (name "/X1") (class "Default")
      (node (ref "C24") (pin "2") (pinfunction "2_2") (pintype "passive"))
      (node (ref "U1") (pin "5") (pinfunction "OSC_IN_5") (pintype "passive"))
      (node (ref "Y1") (pin "2") (pinfunction "OSC2_2") (pintype "passive"))
    )
    (net (code "19") (name "/X2") (class "Default")
      (node (ref "C25") (pin "2") (pinfunction "2_2") (pintype "passive"))
      (node (ref "U1") (pin "6") (pinfunction "OSC_OUT_6") (pintype "passive"))
      (node (ref "Y1") (pin "1") (pinfunction "OSC1_1") (pintype "passive"))
    )
    (net (code "20") (name "GND") (class "Default")
      (node (ref "C10") (pin "1") (pinfunction "1_1") (pintype "passive"))
      (node (ref "C12") (pin "1") (pinfunction "1_1") (pintype "passive"))
      (node (ref "C14") (pin "2") (pinfunction "2_2") (pintype "passive"))
      (node (ref "C15") (pin "1") (pinfunction "1_1") (pintype "passive"))
      (node (ref "C16") (pin "1") (pinfunction "1_1") (pintype "passive"))
      (node (ref "C17") (pin "2") (pinfunction "2_2") (pintype "passive"))
      (node (ref "C18") (pin "1") (pinfunction "1_1") (pintype "passive"))
      (node (ref "C19") (pin "1") (pinfunction "1_1") (pintype "passive"))
      (node (ref "C2") (pin "2") (pinfunction "2_2") (pintype "passive"))
      (node (ref "C20") (pin "1") (pinfunction "1_1") (pintype "passive"))
      (node (ref "C21") (pin "1") (pinfunction "1_1") (pintype "passive"))
      (node (ref "C22") (pin "1") (pinfunction "1_1") (pintype "passive"))
      (node (ref "C23") (pin "1") (pinfunction "1_1") (pintype "passive"))
      (node (ref "C24") (pin "1") (pinfunction "1_1") (pintype "passive"))
      (node (ref "C25") (pin "1") (pinfunction "1_1") (pintype "passive"))
      (node (ref "C26") (pin "1") (pinfunction "1_1") (pintype "passive"))
      (node (ref "C27") (pin "1") (pinfunction "1_1") (pintype "passive"))
      (node (ref "C28") (pin "1") (pinfunction "1_1") (pintype "passive"))
      (node (ref "C29") (pin "1") (pinfunction "1_1") (pintype "passive"))
      (node (ref "C3") (pin "2") (pinfunction "2_2") (pintype "passive"))
      (node (ref "C30") (pin "1") (pinfunction "1_1") (pintype "passive"))
      (node (ref "C31") (pin "1") (pinfunction "1_1") (pintype "passive"))
      (node (ref "C32") (pin "2") (pinfunction "2_2") (pintype "passive"))
      (node (ref "C33") (pin "1") (pinfunction "1_1") (pintype "passive"))
      (node (ref "C34") (pin "1") (pinfunction "1_1") (pintype "passive"))
      (node (ref "C35") (pin "2") (pinfunction "2_2") (pintype "passive"))
      (node (ref "C36") (pin "1") (pinfunction "1_1") (pintype "passive"))
      (node (ref "C37") (pin "1") (pinfunction "1_1") (pintype "passive"))
      (node (ref "C38") (pin "1") (pinfunction "1_1") (pintype "passive"))
      (node (ref "C39") (pin "1") (pinfunction "1_1") (pintype "passive"))
      (node (ref "C4") (pin "2") (pinfunction "2_2") (pintype "passive"))
      (node (ref "C40") (pin "1") (pinfunction "1_1") (pintype "passive"))
      (node (ref "C41") (pin "1") (pinfunction "1_1") (pintype "passive"))
      (node (ref "C42") (pin "2") (pinfunction "2_2") (pintype "passive"))
      (node (ref "C43") (pin "2") (pinfunction "2_2") (pintype "passive"))
      (node (ref "C44") (pin "2") (pinfunction "2_2") (pintype "passive"))
      (node (ref "C5") (pin "2") (pinfunction "2_2") (pintype "passive"))
      (node (ref "C6") (pin "1") (pinfunction "1_1") (pintype "passive"))
      (node (ref "C7") (pin "1") (pinfunction "1_1") (pintype "passive"))
      (node (ref "C8") (pin "1") (pinfunction "1_1") (pintype "passive"))
      (node (ref "C9") (pin "1") (pinfunction "1_1") (pintype "passive"))
      (node (ref "D1") (pin "2") (pinfunction "A_2") (pintype "passive"))
      (node (ref "P1") (pin "1") (pinfunction "1_1") (pintype "passive"))
      (node (ref "P3") (pin "2") (pinfunction "2_2") (pintype "passive"))
      (node (ref "P4") (pin "4") (pinfunction "4_4") (pintype "passive"))
      (node (ref "Q2") (pin "3") (pinfunction "S_3") (pintype "passive"))
      (node (ref "R11") (pin "1") (pinfunction "1_1") (pintype "passive"))
      (node (ref "R14") (pin "2") (pinfunction "2_2") (pintype "passive"))
      (node (ref "R17") (pin "2") (pinfunction "2_2") (pintype "passive"))
      (node (ref "R20") (pin "1") (pinfunction "1_1") (pintype "passive"))
      (node (ref "R23") (pin "2") (pinfunction "2_2") (pintype "passive"))
      (node (ref "R30") (pin "2") (pinfunction "2_2") (pintype "passive"))
      (node (ref "R33") (pin "2") (pinfunction "2_2") (pintype "passive"))
      (node (ref "R9") (pin "2") (pinfunction "2_2") (pintype "passive"))
      (node (ref "S1") (pin "1") (pinfunction "1_1") (pintype "passive"))
      (node (ref "S2") (pin "1") (pinfunction "1_1") (pintype "passive"))
      (node (ref "S3") (pin "1") (pinfunction "1_1") (pintype "passive"))
      (node (ref "S4") (pin "1") (pinfunction "1_1") (pintype "passive"))
      (node (ref "S5") (pin "1") (pinfunction "1_1") (pintype "passive"))
      (node (ref "U1") (pin "23") (pinfunction "VSS_1_23") (pintype "passive"))
      (node (ref "U1") (pin "35") (pinfunction "VSS_2_35") (pintype "passive"))
      (node (ref "U1") (pin "47") (pinfunction "VSS_3_47") (pintype "passive"))
      (node (ref "U1") (pin "8") (pinfunction "VSSA_8") (pintype "passive"))
      (node (ref "U2") (pin "2") (pinfunction "GND_2") (pintype "passive"))
      (node (ref "U3") (pin "2") (pinfunction "GND_2") (pintype "passive"))
      (node (ref "U4") (pin "6") (pinfunction "GND_6") (pintype "passive"))
      (node (ref "U5") (pin "4") (pinfunction "V-_4") (pintype "power_in"))
      (node (ref "U6") (pin "1") (pinfunction "GND_1") (pintype "passive"))
      (node (ref "U7") (pin "1") (pinfunction "GND_1") (pintype "passive"))
      (node (ref "U8") (pin "2") (pinfunction "GND_2") (pintype "passive"))
      (node (ref "U9") (pin "2") (pinfunction "A_2") (pintype "passive"))
    )
    (net (code "21") (name "Net-(C1-Pad2)") (class "Default")
      (node (ref "C1") (pin "2") (pinfunction "2_2") (pintype "passive"))
      (node (ref "R1") (pin "1") (pinfunction "1_1") (pintype "passive"))
    )
    (net (code "22") (name "Net-(C4-Pad1)") (class "Default")
      (node (ref "C4") (pin "1") (pinfunction "1_1") (pintype "passive"))
      (node (ref "C5") (pin "1") (pinfunction "1_1") (pintype "passive"))
      (node (ref "C8") (pin "2") (pinfunction "2_2") (pintype "passive"))
      (node (ref "C9") (pin "2") (pinfunction "2_2") (pintype "passive"))
      (node (ref "L1") (pin "2") (pinfunction "2_2") (pintype "passive"))
      (node (ref "P2") (pin "1") (pinfunction "1_1") (pintype "passive"))
      (node (ref "R6") (pin "2") (pinfunction "2_2") (pintype "passive"))
    )
    (net (code "23") (name "Net-(C10-Pad2)") (class "Default")
      (node (ref "C10") (pin "2") (pinfunction "2_2") (pintype "passive"))
      (node (ref "R2") (pin "1") (pinfunction "1_1") (pintype "passive"))
    )
    (net (code "24") (name "Net-(C11-Pad1)") (class "Default")
      (node (ref "C11") (pin "1") (pinfunction "1_1") (pintype "passive"))
      (node (ref "R17") (pin "1") (pinfunction "1_1") (pintype "passive"))
      (node (ref "R18") (pin "2") (pinfunction "2_2") (pintype "passive"))
    )
    (net (code "25") (name "Net-(C11-Pad2)") (class "Default")
      (node (ref "C11") (pin "2") (pinfunction "2_2") (pintype "passive"))
      (node (ref "R4") (pin "1") (pinfunction "1_1") (pintype "passive"))
      (node (ref "R5") (pin "2") (pinfunction "2_2") (pintype "passive"))
    )
    (net (code "26") (name "Net-(D1-K)") (class "Default")
      (node (ref "C1") (pin "1") (pinfunction "1_1") (pintype "passive"))
      (node (ref "C13") (pin "2") (pinfunction "2_2") (pintype "passive"))
      (node (ref "D1") (pin "1") (pinfunction "K_1") (pintype "passive"))
      (node (ref "L1") (pin "1") (pinfunction "1_1") (pintype "passive"))
      (node (ref "Q1") (pin "3") (pinfunction "S_3") (pintype "passive"))
      (node (ref "Q2") (pin "2") (pinfunction "D_2") (pintype "passive"))
      (node (ref "R2") (pin "2") (pinfunction "2_2") (pintype "passive"))
      (node (ref "R32") (pin "1") (pinfunction "1_1") (pintype "passive"))
      (node (ref "U4") (pin "7") (pinfunction "PHASE_7") (pintype "passive"))
    )
    (net (code "27") (name "Net-(D2-A)") (class "Default")
      (node (ref "D2") (pin "1") (pinfunction "A_1") (pintype "passive"))
      (node (ref "R21") (pin "2") (pinfunction "2_2") (pintype "passive"))
      (node (ref "R23") (pin "1") (pinfunction "1_1") (pintype "passive"))
      (node (ref "U5") (pin "5") (pinfunction "+_5") (pintype "passive"))
    )
    (net (code "28") (name "Net-(D3-A)") (class "Default")
      (node (ref "D3") (pin "1") (pinfunction "A_1") (pintype "passive"))
      (node (ref "P5") (pin "2") (pinfunction "2_2") (pintype "passive"))
      (node (ref "R30") (pin "1") (pinfunction "1_1") (pintype "passive"))
      (node (ref "U5") (pin "3") (pinfunction "+_3") (pintype "passive"))
    )
    (net (code "29") (name "Net-(P2-Pad2)") (class "Default")
      (node (ref "P2") (pin "2") (pinfunction "2_2") (pintype "passive"))
      (node (ref "R11") (pin "2") (pinfunction "2_2") (pintype "passive"))
      (node (ref "R4") (pin "2") (pinfunction "2_2") (pintype "passive"))
    )
    (net (code "30") (name "Net-(Q1-G)") (class "Default")
      (node (ref "Q1") (pin "1") (pinfunction "G_1") (pintype "passive"))
      (node (ref "R32") (pin "2") (pinfunction "2_2") (pintype "passive"))
      (node (ref "R8") (pin "2") (pinfunction "2_2") (pintype "passive"))
    )
    (net (code "31") (name "Net-(Q2-G)") (class "Default")
      (node (ref "Q2") (pin "1") (pinfunction "G_1") (pintype "passive"))
      (node (ref "R15") (pin "1") (pinfunction "1_1") (pintype "passive"))
      (node (ref "R33") (pin "1") (pinfunction "1_1") (pintype "passive"))
    )
    (net (code "32") (name "Net-(U1-BOOT0)") (class "Default")
      (node (ref "R9") (pin "1") (pinfunction "1_1") (pintype "passive"))
      (node (ref "U1") (pin "44") (pinfunction "BOOT0_44") (pintype "passive"))
    )
    (net (code "33") (name "Net-(U1-VDDA)") (class "Default")
      (node (ref "C18") (pin "2") (pinfunction "2_2") (pintype "passive"))
      (node (ref "C19") (pin "2") (pinfunction "2_2") (pintype "passive"))
      (node (ref "R16") (pin "1") (pinfunction "1_1") (pintype "passive"))
      (node (ref "U1") (pin "9") (pinfunction "VDDA_9") (pintype "passive"))
    )
    (net (code "34") (name "Net-(U2-IN+)") (class "Default")
      (node (ref "R3") (pin "1") (pinfunction "1_1") (pintype "passive"))
      (node (ref "R5") (pin "1") (pinfunction "1_1") (pintype "passive"))
      (node (ref "U2") (pin "3") (pinfunction "IN+_3") (pintype "passive"))
    )
    (net (code "35") (name "Net-(U2-IN-)") (class "Default")
      (node (ref "R18") (pin "1") (pinfunction "1_1") (pintype "passive"))
      (node (ref "R19") (pin "2") (pinfunction "2_2") (pintype "passive"))
      (node (ref "U2") (pin "4") (pinfunction "IN-_4") (pintype "passive"))
    )
    (net (code "36") (name "Net-(U2-OUT)") (class "Default")
      (node (ref "R19") (pin "1") (pinfunction "1_1") (pintype "passive"))
      (node (ref "R7") (pin "1") (pinfunction "1_1") (pintype "passive"))
      (node (ref "U2") (pin "1") (pinfunction "OUT_1") (pintype "passive"))
    )
    (net (code "37") (name "Net-(U2-VCC)") (class "Default")
      (node (ref "C15") (pin "2") (pinfunction "2_2") (pintype "passive"))
      (node (ref "R12") (pin "2") (pinfunction "2_2") (pintype "passive"))
      (node (ref "U2") (pin "5") (pinfunction "VCC_5") (pintype "passive"))
    )
    (net (code "38") (name "Net-(U3-IN+)") (class "Default")
      (node (ref "R20") (pin "2") (pinfunction "2_2") (pintype "passive"))
      (node (ref "R6") (pin "1") (pinfunction "1_1") (pintype "passive"))
      (node (ref "U3") (pin "3") (pinfunction "IN+_3") (pintype "passive"))
    )
    (net (code "39") (name "Net-(U3-IN-)") (class "Default")
      (node (ref "R13") (pin "1") (pinfunction "1_1") (pintype "passive"))
      (node (ref "U3") (pin "1") (pinfunction "OUT_1") (pintype "passive"))
      (node (ref "U3") (pin "4") (pinfunction "IN-_4") (pintype "passive"))
    )
    (net (code "40") (name "Net-(U4-BOOT)") (class "Default")
      (node (ref "C13") (pin "1") (pinfunction "1_1") (pintype "passive"))
      (node (ref "U4") (pin "1") (pinfunction "BOOT_1") (pintype "passive"))
    )
    (net (code "41") (name "Net-(U4-EN)") (class "Default")
      (node (ref "R10") (pin "2") (pinfunction "2_2") (pintype "passive"))
      (node (ref "R14") (pin "1") (pinfunction "1_1") (pintype "passive"))
      (node (ref "U4") (pin "3") (pinfunction "EN_3") (pintype "passive"))
    )
    (net (code "42") (name "Net-(U4-LGATE)") (class "Default")
      (node (ref "R15") (pin "2") (pinfunction "2_2") (pintype "passive"))
      (node (ref "U4") (pin "5") (pinfunction "LGATE_5") (pintype "passive"))
    )
    (net (code "43") (name "Net-(U4-UGATE)") (class "Default")
      (node (ref "R8") (pin "1") (pinfunction "1_1") (pintype "passive"))
      (node (ref "U4") (pin "8") (pinfunction "UGATE_8") (pintype "passive"))
    )
    (net (code "44") (name "Net-(U5A--)") (class "Default")
      (node (ref "R29") (pin "1") (pinfunction "1_1") (pintype "passive"))
      (node (ref "U5") (pin "1") (pinfunction "OUT1_1") (pintype "passive"))
      (node (ref "U5") (pin "2") (pinfunction "-_2") (pintype "passive"))
    )
    (net (code "45") (name "Net-(U5B--)") (class "Default")
      (node (ref "R22") (pin "1") (pinfunction "1_1") (pintype "passive"))
      (node (ref "U5") (pin "6") (pinfunction "-_6") (pintype "passive"))
      (node (ref "U5") (pin "7") (pinfunction "OUT2_7") (pintype "passive"))
    )
    (net (code "46") (name "VIN") (class "Default")
      (node (ref "C2") (pin "1") (pinfunction "1_1") (pintype "passive"))
      (node (ref "C42") (pin "1") (pinfunction "1_1") (pintype "passive"))
      (node (ref "C43") (pin "1") (pinfunction "1_1") (pintype "passive"))
      (node (ref "C6") (pin "2") (pinfunction "2_2") (pintype "passive"))
      (node (ref "C7") (pin "2") (pinfunction "2_2") (pintype "passive"))
      (node (ref "P1") (pin "2") (pinfunction "2_2") (pintype "passive"))
      (node (ref "P5") (pin "1") (pinfunction "1_1") (pintype "passive"))
      (node (ref "Q1") (pin "2") (pinfunction "D_2") (pintype "passive"))
      (node (ref "R1") (pin "2") (pinfunction "2_2") (pintype "passive"))
      (node (ref "R21") (pin "1") (pinfunction "1_1") (pintype "passive"))
      (node (ref "U8") (pin "3") (pinfunction "VIN_3") (pintype "passive"))
    )
    (net (code "47") (name "Vref_1.2V") (class "Default")
      (node (ref "C41") (pin "2") (pinfunction "2_2") (pintype "passive"))
      (node (ref "R3") (pin "2") (pinfunction "2_2") (pintype "passive"))
      (node (ref "R31") (pin "1") (pinfunction "1_1") (pintype "passive"))
      (node (ref "U9") (pin "1") (pinfunction "C_1") (pintype "passive"))
    )
    (net (code "48") (name "unconnected-(U1-PA8{slash}T1C1{slash}MCO-Pad29)") (class "Default")
      (node (ref "U1") (pin "29") (pinfunction "PA8/T1C1/MCO_29") (pintype "passive"))
    )
    (net (code "49") (name "unconnected-(U1-PA9{slash}T1C2{slash}USART1_Tx-Pad30)") (class "Default")
      (node (ref "U1") (pin "30") (pinfunction "PA9/T1C2/USART1_Tx_30") (pintype "passive"))
    )
    (net (code "50") (name "unconnected-(U1-PA11{slash}CAN_Rx{slash}T1C4{slash}USBDM-Pad32)") (class "Default")
      (node (ref "U1") (pin "32") (pinfunction "PA11/CAN_Rx/T1C4/USBDM_32") (pintype "passive"))
    )
    (net (code "51") (name "unconnected-(U1-PA12{slash}CAN_Tx{slash}T1ETR{slash}USBDP-Pad33)") (class "Default")
      (node (ref "U1") (pin "33") (pinfunction "PA12/CAN_Tx/T1ETR/USBDP_33") (pintype "passive"))
    )
    (net (code "52") (name "unconnected-(U1-PA15{slash}JTDI{slash}I2S3_WS{slash}JTDI{slash}T2C1ETR{slash}SPI3_NSS-Pad38)") (class "Default")
      (node (ref "U1") (pin "38") (pinfunction "PA15/JTDI/I2S3_WS/JTDI/T2C1ETR/SPI3_NSS_38") (pintype "passive"))
    )
    (net (code "53") (name "unconnected-(U1-PB0{slash}ADC123_IN8{slash}T3C3{slash}T8C2N{slash}T1C2N-Pad18)") (class "Default")
      (node (ref "U1") (pin "18") (pinfunction "PB0/ADC123_IN8/T3C3/T8C2N/T1C2N_18") (pintype "passive"))
    )
    (net (code "54") (name "unconnected-(U1-PB1{slash}ADC123_IN9{slash}T3C4{slash}T8C3N{slash}T1C3N-Pad19)") (class "Default")
      (node (ref "U1") (pin "19") (pinfunction "PB1/ADC123_IN9/T3C4/T8C3N/T1C3N_19") (pintype "passive"))
    )
    (net (code "55") (name "unconnected-(U1-PB2{slash}BOOT1-Pad20)") (class "Default")
      (node (ref "U1") (pin "20") (pinfunction "PB2/BOOT1_20") (pintype "passive"))
    )
    (net (code "56") (name "unconnected-(U1-PB3{slash}JTDO{slash}SPI3_SCK{slash}I2S3_CK{slash}T2C2{slash}SPI1_SCK-Pad39)") (class "Default")
      (node (ref "U1") (pin "39") (pinfunction "PB3/JTDO/SPI3_SCK/I2S3_CK/T2C2/SPI1_SCK_39") (pintype "passive"))
    )
    (net (code "57") (name "unconnected-(U1-PB4{slash}NJTRST{slash}SPI3_MISO{slash}T3C1{slash}SPI1_MISO-Pad40)") (class "Default")
      (node (ref "U1") (pin "40") (pinfunction "PB4/NJTRST/SPI3_MISO/T3C1/SPI1_MISO_40") (pintype "passive"))
    )
    (net (code "58") (name "unconnected-(U1-PB5{slash}I2C1_SMBA{slash}I2S3_SD{slash}SPI3_MOSI{slash}T3C2{slash}SPI1_MOSI-Pad41)") (class "Default")
      (node (ref "U1") (pin "41") (pinfunction "PB5/I2C1_SMBA/I2S3_SD/SPI3_MOSI/T3C2/SPI1_MOSI_41") (pintype "passive"))
    )
    (net (code "59") (name "unconnected-(U1-PB8{slash}SDIO_D4{slash}I2C1_SCL{slash}T4C3(7){slash}CAN_Rx-Pad45)") (class "Default")
      (node (ref "U1") (pin "45") (pinfunction "PB8/SDIO_D4/I2C1_SCL/T4C3(7)/CAN_Rx_45") (pintype "passive"))
    )
    (net (code "60") (name "unconnected-(U1-PB9{slash}SDIO_D5{slash}I2C1_SDA{slash}T4C4{slash}CAN_Tx-Pad46)") (class "Default")
      (node (ref "U1") (pin "46") (pinfunction "PB9/SDIO_D5/I2C1_SDA/T4C4/CAN_Tx_46") (pintype "passive"))
    )
    (net (code "61") (name "unconnected-(U1-PB10{slash}USART3_Tx{slash}I2C2_SCL{slash}T2C3-Pad21)") (class "Default")
      (node (ref "U1") (pin "21") (pinfunction "PB10/USART3_Tx/I2C2_SCL/T2C3_21") (pintype "passive"))
    )
    (net (code "62") (name "unconnected-(U1-PB11{slash}USART3_Rx{slash}I2C2_SDA{slash}T2C4-Pad22)") (class "Default")
      (node (ref "U1") (pin "22") (pinfunction "PB11/USART3_Rx/I2C2_SDA/T2C4_22") (pintype "passive"))
    )
    (net (code "63") (name "unconnected-(U1-PB12{slash}I2S2_WS{slash}T1BKIN{slash}SPI2_NSS{slash}I2C2_SMBA-Pad25)") (class "Default")
      (node (ref "U1") (pin "25") (pinfunction "PB12/I2S2_WS/T1BKIN/SPI2_NSS/I2C2_SMBA_25") (pintype "passive"))
    )
    (net (code "64") (name "unconnected-(U1-PB13{slash}I2S2_CK{slash}T1CH1N{slash}SPI2_SCK-Pad26)") (class "Default")
      (node (ref "U1") (pin "26") (pinfunction "PB13/I2S2_CK/T1CH1N/SPI2_SCK_26") (pintype "passive"))
    )
    (net (code "65") (name "unconnected-(U1-PB14{slash}T1CH2N{slash}SPI2_MISO-Pad27)") (class "Default")
      (node (ref "U1") (pin "27") (pinfunction "PB14/T1CH2N/SPI2_MISO_27") (pintype "passive"))
    )
    (net (code "66") (name "unconnected-(U1-PB15{slash}I2S2_SD{slash}T1CH3N{slash}SPI2_MOSI-Pad28)") (class "Default")
      (node (ref "U1") (pin "28") (pinfunction "PB15/I2S2_SD/T1CH3N/SPI2_MOSI_28") (pintype "passive"))
    )
    (net (code "67") (name "unconnected-(U1-PC13-TAMPER-RTC-Pad2)") (class "Default")
      (node (ref "U1") (pin "2") (pinfunction "PC13-TAMPER-RTC_2") (pintype "passive"))
    )
    (net (code "68") (name "unconnected-(U1-PC14-OSC32_IN-Pad3)") (class "Default")
      (node (ref "U1") (pin "3") (pinfunction "PC14-OSC32_IN_3") (pintype "passive"))
    )
    (net (code "69") (name "unconnected-(U1-PC15-OSC32_OUT-Pad4)") (class "Default")
      (node (ref "U1") (pin "4") (pinfunction "PC15-OSC32_OUT_4") (pintype "passive"))
    )
    (net (code "70") (name "unconnected-(U9-NC-Pad3)") (class "Default")
      (node (ref "U9") (pin "3") (pinfunction "NC_3") (pintype "passive"))
    )
  )
)
